# v1_0.net
KiCad netlist of a schematic drawn in Altium Designer
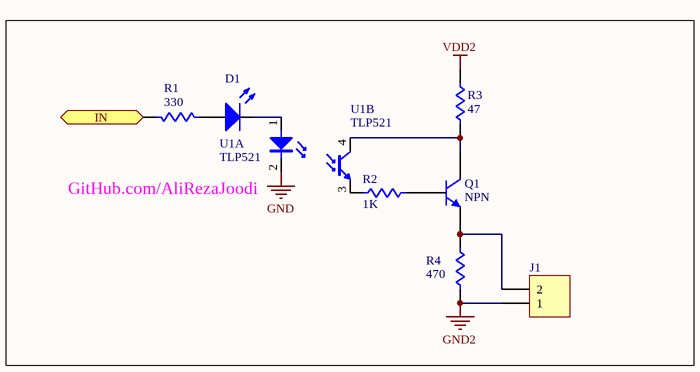
[diagram p0: v1.0.SchDoc]

(export (version "E")
  (design (tool "Eeschema 10.0.6"))
  (components
    (comp (ref "D1")
      (value "YELLOW")
      (footprint "0805_Diode")
      (description "Typical INFRARED GaAs LED")
      (fields (field (name "MANUFACTURER") "Generic Components") (field (name "PUBLISHER") "Altium Limited"))
      (libsource (lib "Miscellaneous Devices") (part "LED"))
    )
    (comp (ref "J1")
      (value "2Pin")
      (footprint "Fonics_2PIN_1")
      (description "Header, 2-Pin")
      (fields (field (name "PUBLISHER") "Altium Limited"))
      (libsource (lib "Miscellaneous Connectors") (part "Header 2"))
    )
    (comp (ref "Q1")
      (value "NPN")
      (footprint "TO-226-AA")
      (description "NPN Bipolar Transistor")
      (fields (field (name "PUBLISHER") "Altium Limited"))
      (libsource (lib "Miscellaneous Devices") (part "NPN"))
    )
    (comp (ref "R1")
      (value "330")
      (footprint "0805")
      (description "Resistor")
      (fields (field (name "MANUFACTURER") "Generic Components") (field (name "PUBLISHER") "Altium Limited"))
      (libsource (lib "Miscellaneous Devices") (part "Res1"))
    )
    (comp (ref "R2")
      (value "1K")
      (footprint "RESC3216N")
      (description "Resistor")
      (fields (field (name "MANUFACTURER") "Generic Components") (field (name "PUBLISHER") "Altium Limited"))
      (libsource (lib "Miscellaneous Devices") (part "Res1"))
    )
    (comp (ref "R3")
      (value "47")
      (footprint "RESC3216N")
      (description "Resistor")
      (fields (field (name "MANUFACTURER") "Generic Components") (field (name "PUBLISHER") "Altium Limited"))
      (libsource (lib "Miscellaneous Devices") (part "Res1"))
    )
    (comp (ref "R4")
      (value "470")
      (footprint "RESC3216N")
      (description "Resistor")
      (fields (field (name "MANUFACTURER") "Generic Components") (field (name "PUBLISHER") "Altium Limited"))
      (libsource (lib "Miscellaneous Devices") (part "Res1"))
    )
    (comp (ref "U1")
      (value "TLP521")
      (footprint "SMD_4PIN")
      (fields (field (name "PUBLISHER") "Altium Limited"))
      (libsource (lib "my Libraries") (part "Optoisolator"))
    )
  )
  (nets
    (net (code "1") (name "/IN") (class "Default")
      (node (ref "R1") (pin "1") (pinfunction "1_1") (pintype "passive"))
    )
    (net (code "2") (name "GND") (class "Default")
      (node (ref "U1") (pin "2") (pinfunction "K_2") (pintype "power_in"))
    )
    (net (code "3") (name "GND2") (class "Default")
      (node (ref "J1") (pin "1") (pinfunction "1_1") (pintype "passive"))
      (node (ref "R4") (pin "2") (pinfunction "2_2") (pintype "passive"))
    )
    (net (code "4") (name "Net-(D1-A)") (class "Default")
      (node (ref "D1") (pin "1") (pinfunction "A_1") (pintype "passive"))
      (node (ref "R1") (pin "2") (pinfunction "2_2") (pintype "passive"))
    )
    (net (code "5") (name "Net-(D1-K)") (class "Default")
      (node (ref "D1") (pin "2") (pinfunction "K_2") (pintype "passive"))
      (node (ref "U1") (pin "1") (pinfunction "A_1") (pintype "power_in"))
    )
    (net (code "6") (name "Net-(Q1-B)") (class "Default")
      (node (ref "Q1") (pin "2") (pinfunction "B_2") (pintype "passive"))
      (node (ref "R2") (pin "2") (pinfunction "2_2") (pintype "passive"))
    )
    (net (code "7") (name "Net-(Q1-C)") (class "Default")
      (node (ref "Q1") (pin "1") (pinfunction "C_1") (pintype "passive"))
      (node (ref "R3") (pin "2") (pinfunction "2_2") (pintype "passive"))
      (node (ref "U1") (pin "4") (pinfunction "C_4") (pintype "passive"))
    )
    (net (code "8") (name "Net-(Q1-E)") (class "Default")
      (node (ref "J1") (pin "2") (pinfunction "2_2") (pintype "passive"))
      (node (ref "Q1") (pin "3") (pinfunction "E_3") (pintype "passive"))
      (node (ref "R4") (pin "1") (pinfunction "1_1") (pintype "passive"))
    )
    (net (code "9") (name "Net-(U1B-E)") (class "Default")
      (node (ref "R2") (pin "1") (pinfunction "1_1") (pintype "passive"))
      (node (ref "U1") (pin "3") (pinfunction "E_3") (pintype "passive"))
    )
    (net (code "10") (name "VDD2") (class "Default")
      (node (ref "R3") (pin "1") (pinfunction "1_1") (pintype "passive"))
    )
  )
)
